# schematic-version4_-_Jingbin.net
KiCad netlist of a schematic drawn in EAGLE
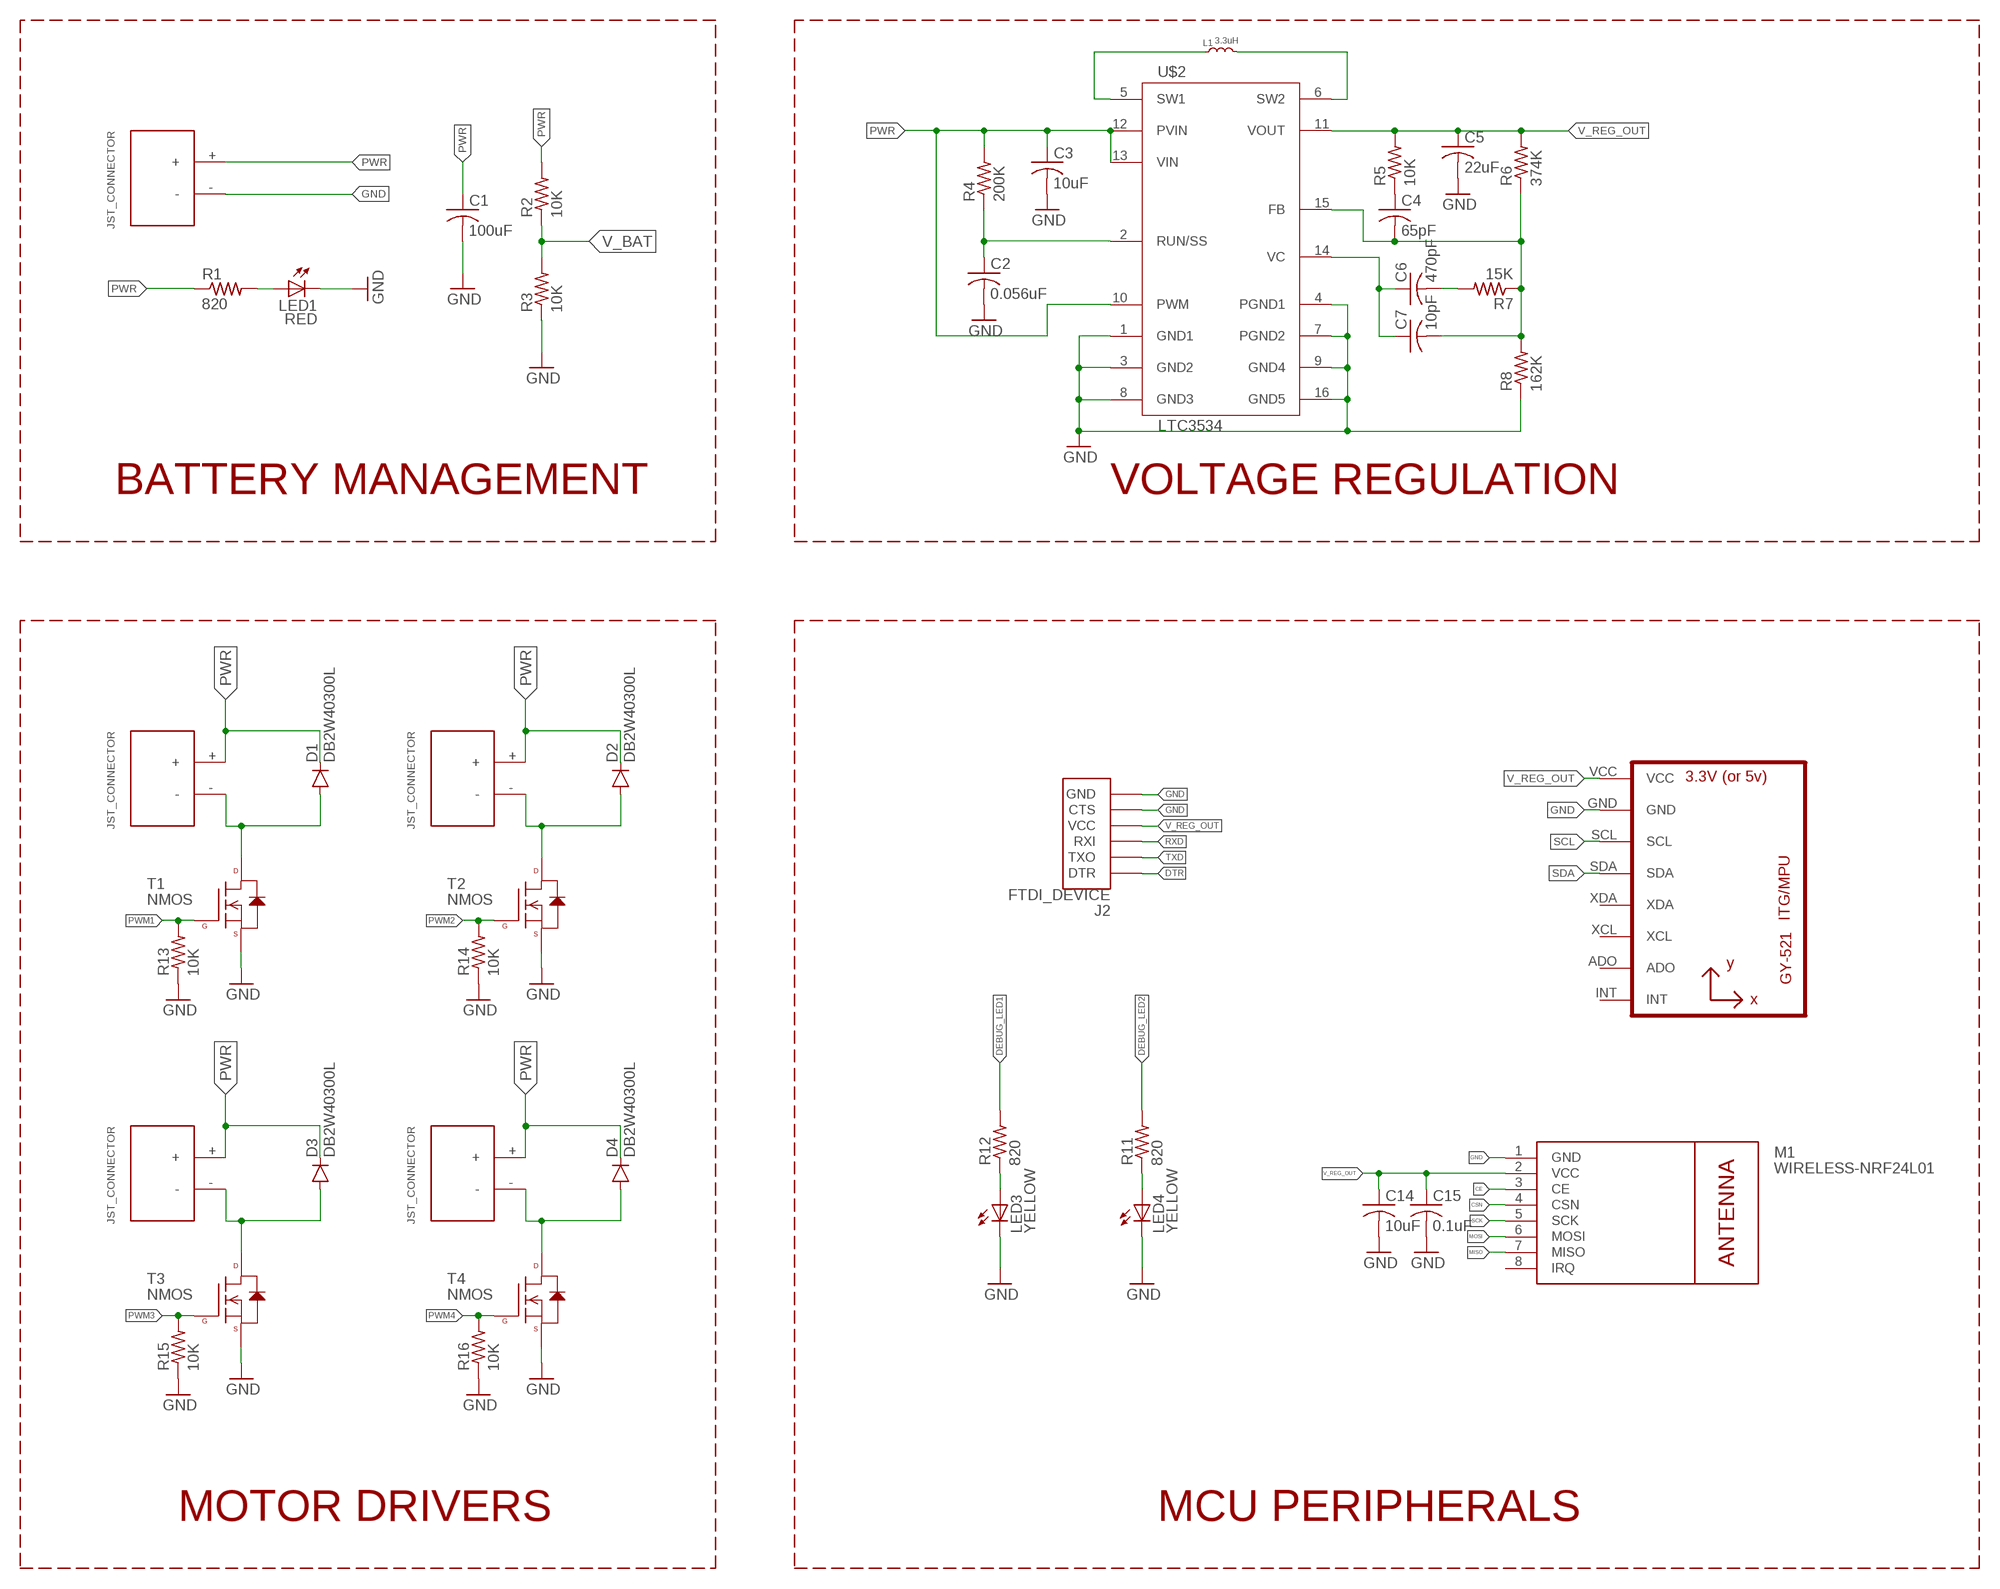
[diagram p0: schematic, sheet 1, part 1 of 2]
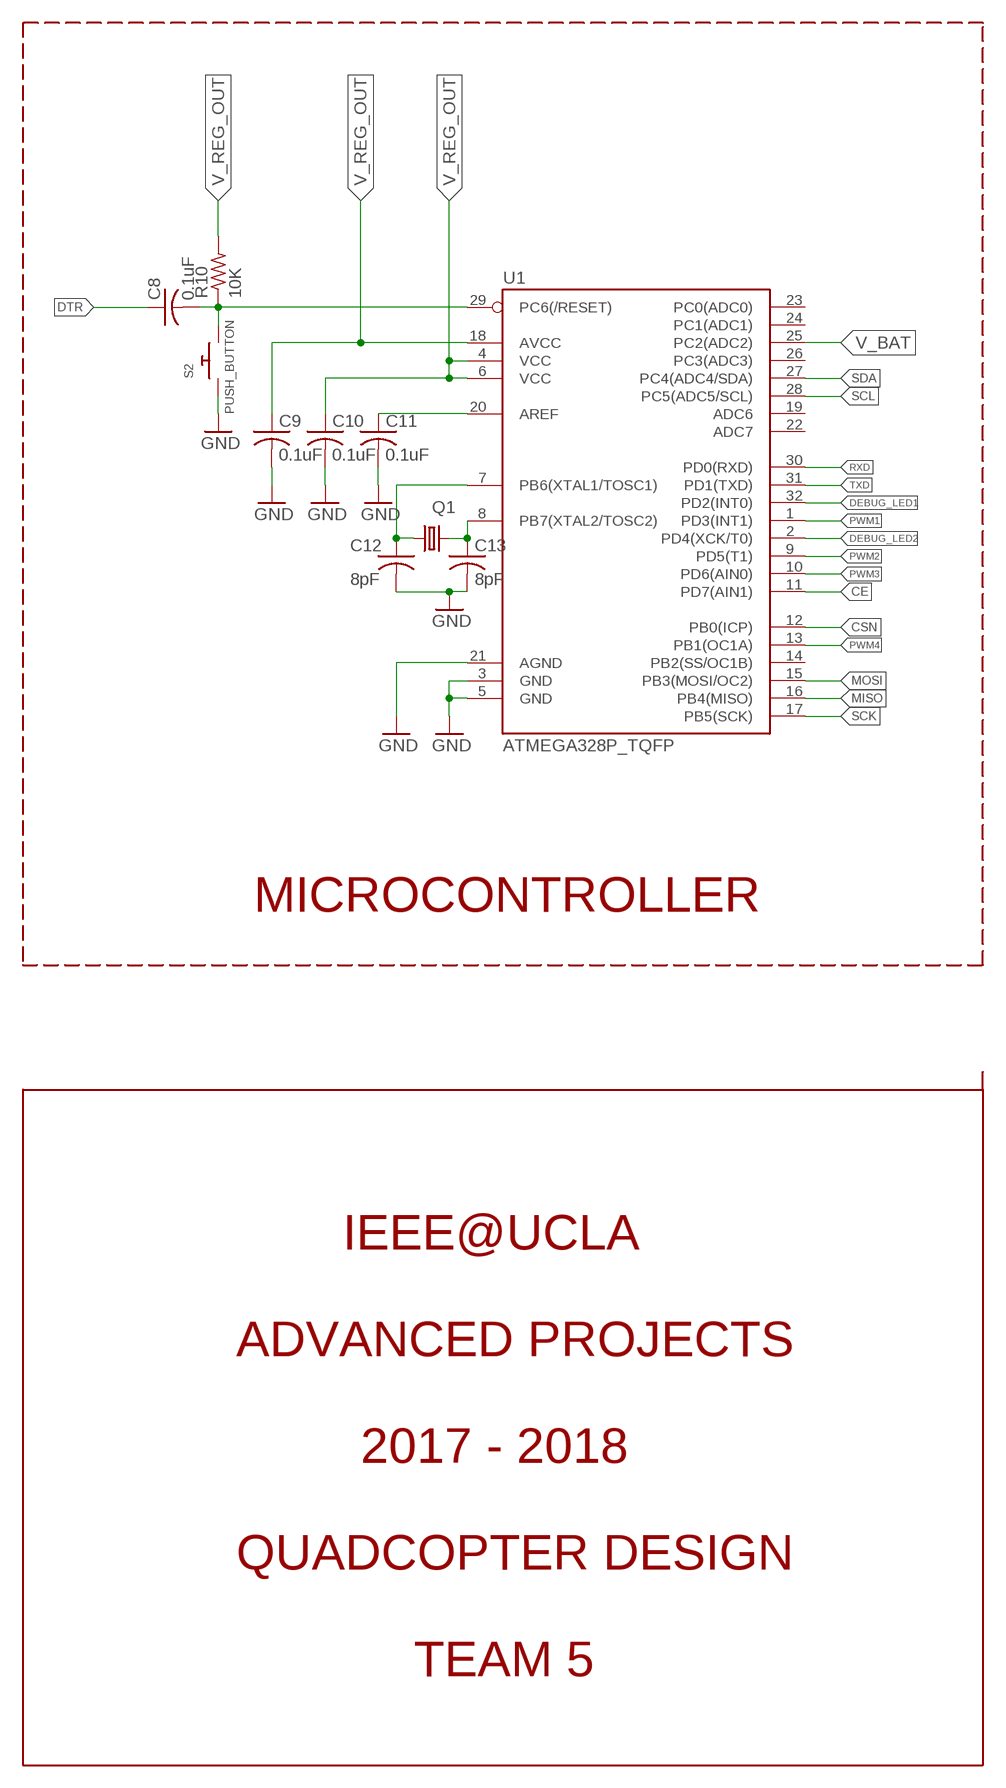
[diagram p1: schematic, sheet 1, part 2 of 2]

(export (version "E")
  (design (tool "Eeschema 10.0.6"))
  (components
    (comp (ref "C1")
      (value "100uF")
      (footprint "eagle-import:C1206")
      (libsource (lib "eagle-import") (part "C-USC1206"))
    )
    (comp (ref "C2")
      (value "0.056uF")
      (footprint "eagle-import:C0603")
      (libsource (lib "eagle-import") (part "resistor_348_C-USC0603"))
    )
    (comp (ref "C3")
      (value "10uF")
      (footprint "eagle-import:C0603")
      (libsource (lib "eagle-import") (part "resistor_348_C-USC0603"))
    )
    (comp (ref "C4")
      (value "65pF")
      (footprint "eagle-import:C1206")
      (libsource (lib "eagle-import") (part "C-USC1206"))
    )
    (comp (ref "C5")
      (value "22uF")
      (footprint "eagle-import:C0603")
      (libsource (lib "eagle-import") (part "resistor_348_C-USC0603"))
    )
    (comp (ref "C6")
      (value "470pF")
      (footprint "eagle-import:C0603")
      (libsource (lib "eagle-import") (part "resistor_348_C-USC0603"))
    )
    (comp (ref "C7")
      (value "10pF")
      (footprint "eagle-import:C0603")
      (libsource (lib "eagle-import") (part "resistor_348_C-USC0603"))
    )
    (comp (ref "C8")
      (value "0.1uF")
      (footprint "eagle-import:C0603")
      (libsource (lib "eagle-import") (part "C-USC0603"))
    )
    (comp (ref "C9")
      (value "0.1uF")
      (footprint "eagle-import:C0603")
      (libsource (lib "eagle-import") (part "C-USC0603"))
    )
    (comp (ref "C10")
      (value "0.1uF")
      (footprint "eagle-import:C0603")
      (libsource (lib "eagle-import") (part "C-USC0603"))
    )
    (comp (ref "C11")
      (value "0.1uF")
      (footprint "eagle-import:C0603")
      (libsource (lib "eagle-import") (part "C-USC0603"))
    )
    (comp (ref "C12")
      (value "8pF")
      (footprint "eagle-import:C0603")
      (libsource (lib "eagle-import") (part "resistor_348_C-USC0603"))
    )
    (comp (ref "C13")
      (value "8pF")
      (footprint "eagle-import:C0603")
      (libsource (lib "eagle-import") (part "resistor_348_C-USC0603"))
    )
    (comp (ref "C14")
      (value "10uF")
      (footprint "eagle-import:C0603")
      (libsource (lib "eagle-import") (part "resistor_348_C-USC0603"))
    )
    (comp (ref "C15")
      (value "0.1uF")
      (footprint "eagle-import:C0603")
      (libsource (lib "eagle-import") (part "resistor_348_C-USC0603"))
    )
    (comp (ref "D1")
      (value "DB2W40300L")
      (footprint "eagle-import:MINI2-F3-B")
      (libsource (lib "eagle-import") (part "DB2W40300L"))
    )
    (comp (ref "D2")
      (value "DB2W40300L")
      (footprint "eagle-import:MINI2-F3-B")
      (libsource (lib "eagle-import") (part "DB2W40300L"))
    )
    (comp (ref "D3")
      (value "DB2W40300L")
      (footprint "eagle-import:MINI2-F3-B")
      (libsource (lib "eagle-import") (part "DB2W40300L"))
    )
    (comp (ref "D4")
      (value "DB2W40300L")
      (footprint "eagle-import:MINI2-F3-B")
      (libsource (lib "eagle-import") (part "DB2W40300L"))
    )
    (comp (ref "J2")
      (value "FTDI_DEVICE")
      (footprint "eagle-import:FTDI_DEVICE_SIDE")
      (libsource (lib "eagle-import") (part "FTDI_DEVICE"))
    )
    (comp (ref "L1")
      (value "3.3uH")
      (footprint "eagle-import:XAL4020")
      (libsource (lib "eagle-import") (part "INDUCTOR.XAL4020"))
    )
    (comp (ref "LED1")
      (value "RED")
      (footprint "eagle-import:SML0603")
      (libsource (lib "eagle-import") (part "LEDSML0603"))
    )
    (comp (ref "LED3")
      (value "YELLOW")
      (footprint "eagle-import:SML0603")
      (libsource (lib "eagle-import") (part "LEDSML0603"))
    )
    (comp (ref "LED4")
      (value "YELLOW")
      (footprint "eagle-import:SML0603")
      (libsource (lib "eagle-import") (part "LEDSML0603"))
    )
    (comp (ref "M1")
      (value "WIRELESS-NRF24L01")
      (footprint "eagle-import:WIRELESS-NRF24L01")
      (libsource (lib "eagle-import") (part "WIRELESS-NRF24L01"))
    )
    (comp (ref "Q1")
      (value "NX3225GD")
      (footprint "eagle-import:NX3225GD-CRA-3")
      (libsource (lib "eagle-import") (part "NX3225GD"))
    )
    (comp (ref "R1")
      (value "820")
      (footprint "eagle-import:R0603")
      (libsource (lib "eagle-import") (part "R-US_R0603"))
    )
    (comp (ref "R2")
      (value "10K")
      (footprint "eagle-import:R0603")
      (libsource (lib "eagle-import") (part "resistor_348_R-US_R0603"))
    )
    (comp (ref "R3")
      (value "10K")
      (footprint "eagle-import:R0603")
      (libsource (lib "eagle-import") (part "resistor_348_R-US_R0603"))
    )
    (comp (ref "R4")
      (value "200K")
      (footprint "eagle-import:R0603")
      (libsource (lib "eagle-import") (part "resistor_348_R-US_R0603"))
    )
    (comp (ref "R5")
      (value "10K")
      (footprint "eagle-import:R0603")
      (libsource (lib "eagle-import") (part "resistor_348_R-US_R0603"))
    )
    (comp (ref "R6")
      (value "374K")
      (footprint "eagle-import:R0603")
      (libsource (lib "eagle-import") (part "resistor_348_R-US_R0603"))
    )
    (comp (ref "R7")
      (value "15K")
      (footprint "eagle-import:R0603")
      (libsource (lib "eagle-import") (part "resistor_348_R-US_R0603"))
    )
    (comp (ref "R8")
      (value "162K")
      (footprint "eagle-import:R0603")
      (libsource (lib "eagle-import") (part "resistor_348_R-US_R0603"))
    )
    (comp (ref "R10")
      (value "10K")
      (footprint "eagle-import:R0603")
      (libsource (lib "eagle-import") (part "resistor_348_R-US_R0603"))
    )
    (comp (ref "R11")
      (value "820")
      (footprint "eagle-import:R0603")
      (libsource (lib "eagle-import") (part "R-US_R0603"))
    )
    (comp (ref "R12")
      (value "820")
      (footprint "eagle-import:R0603")
      (libsource (lib "eagle-import") (part "R-US_R0603"))
    )
    (comp (ref "R13")
      (value "10K")
      (footprint "eagle-import:R0603")
      (libsource (lib "eagle-import") (part "resistor_348_R-US_R0603"))
    )
    (comp (ref "R14")
      (value "10K")
      (footprint "eagle-import:R0603")
      (libsource (lib "eagle-import") (part "resistor_348_R-US_R0603"))
    )
    (comp (ref "R15")
      (value "10K")
      (footprint "eagle-import:R0603")
      (libsource (lib "eagle-import") (part "resistor_348_R-US_R0603"))
    )
    (comp (ref "R16")
      (value "10K")
      (footprint "eagle-import:R0603")
      (libsource (lib "eagle-import") (part "resistor_348_R-US_R0603"))
    )
    (comp (ref "S2")
      (value "PUSH_BUTTON")
      (footprint "eagle-import:PUSHBUTTON_SMD_SJ")
      (libsource (lib "eagle-import") (part "SWITCH_PUSHBUTTONSOFTTOUCHSMD_SJ"))
    )
    (comp (ref "T1")
      (value "NMOS")
      (footprint "eagle-import:SOT23-3")
      (libsource (lib "eagle-import") (part "N-CHANNEL-MOSFET-IRLML6244TRPBF"))
    )
    (comp (ref "T2")
      (value "NMOS")
      (footprint "eagle-import:SOT23-3")
      (libsource (lib "eagle-import") (part "N-CHANNEL-MOSFET-IRLML6244TRPBF"))
    )
    (comp (ref "T3")
      (value "NMOS")
      (footprint "eagle-import:SOT23-3")
      (libsource (lib "eagle-import") (part "N-CHANNEL-MOSFET-IRLML6244TRPBF"))
    )
    (comp (ref "T4")
      (value "NMOS")
      (footprint "eagle-import:SOT23-3")
      (libsource (lib "eagle-import") (part "N-CHANNEL-MOSFET-IRLML6244TRPBF"))
    )
    (comp (ref "U$1")
      (value "JST_CONNECTOR_FEMALE")
      (footprint "eagle-import:JST_CONNECTOR_FEMALE")
      (libsource (lib "eagle-import") (part "JST_CONNECTOR_FEMALE"))
    )
    (comp (ref "U$2")
      (value "LTC3534")
      (footprint "eagle-import:SSOP-16GN")
      (libsource (lib "eagle-import") (part "LTC3534"))
    )
    (comp (ref "U$4")
      (value "JST_CONNECTOR_FEMALE")
      (footprint "eagle-import:JST_CONNECTOR_FEMALE")
      (libsource (lib "eagle-import") (part "JST_CONNECTOR_FEMALE"))
    )
    (comp (ref "U$7")
      (value "JST_CONNECTOR_FEMALE")
      (footprint "eagle-import:JST_CONNECTOR_FEMALE")
      (libsource (lib "eagle-import") (part "JST_CONNECTOR_FEMALE"))
    )
    (comp (ref "U$10")
      (value "JST_CONNECTOR_FEMALE")
      (footprint "eagle-import:JST_CONNECTOR_FEMALE")
      (libsource (lib "eagle-import") (part "JST_CONNECTOR_FEMALE"))
    )
    (comp (ref "U$13")
      (value "JST_CONNECTOR_FEMALE")
      (footprint "eagle-import:JST_CONNECTOR_FEMALE")
      (libsource (lib "eagle-import") (part "JST_CONNECTOR_FEMALE"))
    )
    (comp (ref "U1")
      (value "ATMEGA328P_TQFP")
      (footprint "eagle-import:TQFP32-08")
      (libsource (lib "eagle-import") (part "ATMEGA328P_TQFP"))
    )
    (comp (ref "U2")
      (value "GY-521MPU6050")
      (footprint "eagle-import:GY-521")
      (libsource (lib "eagle-import") (part "GY-521MPU6050"))
    )
  )
  (nets
    (net (code "1") (name "CE") (class "Default")
      (node (ref "M1") (pin "3") (pinfunction "CE_3") (pintype "bidirectional"))
      (node (ref "U1") (pin "11") (pinfunction "PD7(AIN1)_11") (pintype "bidirectional"))
    )
    (net (code "2") (name "CSN") (class "Default")
      (node (ref "M1") (pin "4") (pinfunction "CSN_4") (pintype "bidirectional"))
      (node (ref "U1") (pin "12") (pinfunction "PB0(ICP)_12") (pintype "bidirectional"))
    )
    (net (code "3") (name "DEBUG_LED1") (class "Default")
      (node (ref "R12") (pin "2") (pinfunction "2_2") (pintype "passive"))
      (node (ref "U1") (pin "32") (pinfunction "PD2(INT0)_32") (pintype "bidirectional"))
    )
    (net (code "4") (name "DEBUG_LED2") (class "Default")
      (node (ref "R11") (pin "2") (pinfunction "2_2") (pintype "passive"))
      (node (ref "U1") (pin "2") (pinfunction "PD4(XCK/T0)_2") (pintype "bidirectional"))
    )
    (net (code "5") (name "DTR") (class "Default")
      (node (ref "C8") (pin "1") (pinfunction "1_1") (pintype "passive"))
      (node (ref "J2") (pin "P$1") (pinfunction "DTR_P$1") (pintype "bidirectional"))
    )
    (net (code "6") (name "GND") (class "Default")
      (node (ref "C1") (pin "2") (pinfunction "2_2") (pintype "passive"))
      (node (ref "C10") (pin "2") (pinfunction "2_2") (pintype "passive"))
      (node (ref "C11") (pin "2") (pinfunction "2_2") (pintype "passive"))
      (node (ref "C12") (pin "2") (pinfunction "2_2") (pintype "passive"))
      (node (ref "C13") (pin "2") (pinfunction "2_2") (pintype "passive"))
      (node (ref "C14") (pin "2") (pinfunction "2_2") (pintype "passive"))
      (node (ref "C15") (pin "2") (pinfunction "2_2") (pintype "passive"))
      (node (ref "C2") (pin "2") (pinfunction "2_2") (pintype "passive"))
      (node (ref "C3") (pin "2") (pinfunction "2_2") (pintype "passive"))
      (node (ref "C5") (pin "2") (pinfunction "2_2") (pintype "passive"))
      (node (ref "C9") (pin "2") (pinfunction "2_2") (pintype "passive"))
      (node (ref "J2") (pin "P$5") (pinfunction "CTS_P$5") (pintype "bidirectional"))
      (node (ref "J2") (pin "P$6") (pinfunction "GND_P$6") (pintype "bidirectional"))
      (node (ref "LED1") (pin "C") (pinfunction "C_C") (pintype "passive"))
      (node (ref "LED3") (pin "C") (pinfunction "C_C") (pintype "passive"))
      (node (ref "LED4") (pin "C") (pinfunction "C_C") (pintype "passive"))
      (node (ref "M1") (pin "1") (pinfunction "GND_1") (pintype "power_in"))
      (node (ref "R13") (pin "1") (pinfunction "1_1") (pintype "passive"))
      (node (ref "R14") (pin "1") (pinfunction "1_1") (pintype "passive"))
      (node (ref "R15") (pin "1") (pinfunction "1_1") (pintype "passive"))
      (node (ref "R16") (pin "1") (pinfunction "1_1") (pintype "passive"))
      (node (ref "R3") (pin "1") (pinfunction "1_1") (pintype "passive"))
      (node (ref "R8") (pin "1") (pinfunction "1_1") (pintype "passive"))
      (node (ref "S2") (pin "P$1") (pinfunction "P$1_P$1") (pintype "passive"))
      (node (ref "T1") (pin "2") (pinfunction "S_2") (pintype "passive"))
      (node (ref "T2") (pin "2") (pinfunction "S_2") (pintype "passive"))
      (node (ref "T3") (pin "2") (pinfunction "S_2") (pintype "passive"))
      (node (ref "T4") (pin "2") (pinfunction "S_2") (pintype "passive"))
      (node (ref "U$1") (pin "-") (pinfunction "-_-") (pintype "bidirectional"))
      (node (ref "U$2") (pin "1") (pinfunction "GND1_1") (pintype "bidirectional"))
      (node (ref "U$2") (pin "16") (pinfunction "GND5_16") (pintype "bidirectional"))
      (node (ref "U$2") (pin "3") (pinfunction "GND2_3") (pintype "bidirectional"))
      (node (ref "U$2") (pin "4") (pinfunction "PGND1_4") (pintype "bidirectional"))
      (node (ref "U$2") (pin "7") (pinfunction "PGND2_7") (pintype "bidirectional"))
      (node (ref "U$2") (pin "8") (pinfunction "GND3_8") (pintype "bidirectional"))
      (node (ref "U$2") (pin "9") (pinfunction "GND4_9") (pintype "bidirectional"))
      (node (ref "U1") (pin "21") (pinfunction "AGND_21") (pintype "bidirectional"))
      (node (ref "U1") (pin "3") (pinfunction "GND_3") (pintype "bidirectional"))
      (node (ref "U1") (pin "5") (pinfunction "GND_5") (pintype "bidirectional"))
      (node (ref "U2") (pin "GND") (pinfunction "GND_GND") (pintype "bidirectional"))
    )
    (net (code "7") (name "MISO") (class "Default")
      (node (ref "M1") (pin "7") (pinfunction "MISO_7") (pintype "bidirectional"))
      (node (ref "U1") (pin "16") (pinfunction "PB4(MISO)_16") (pintype "bidirectional"))
    )
    (net (code "8") (name "MOSI") (class "Default")
      (node (ref "M1") (pin "6") (pinfunction "MOSI_6") (pintype "bidirectional"))
      (node (ref "U1") (pin "15") (pinfunction "PB3(MOSI/OC2)_15") (pintype "bidirectional"))
    )
    (net (code "9") (name "Net-(C4-Pad1)") (class "Default")
      (node (ref "C4") (pin "1") (pinfunction "1_1") (pintype "passive"))
      (node (ref "R5") (pin "1") (pinfunction "1_1") (pintype "passive"))
    )
    (net (code "10") (name "Net-(C6-Pad2)") (class "Default")
      (node (ref "C6") (pin "2") (pinfunction "2_2") (pintype "passive"))
      (node (ref "R7") (pin "2") (pinfunction "2_2") (pintype "passive"))
    )
    (net (code "11") (name "Net-(D1-PPIN)") (class "Default")
      (node (ref "D1") (pin "POS") (pinfunction "PPIN_POS") (pintype "passive"))
      (node (ref "T1") (pin "3") (pinfunction "D_3") (pintype "passive"))
      (node (ref "U$4") (pin "-") (pinfunction "-_-") (pintype "bidirectional"))
    )
    (net (code "12") (name "Net-(D2-PPIN)") (class "Default")
      (node (ref "D2") (pin "POS") (pinfunction "PPIN_POS") (pintype "passive"))
      (node (ref "T2") (pin "3") (pinfunction "D_3") (pintype "passive"))
      (node (ref "U$7") (pin "-") (pinfunction "-_-") (pintype "bidirectional"))
    )
    (net (code "13") (name "Net-(D3-PPIN)") (class "Default")
      (node (ref "D3") (pin "POS") (pinfunction "PPIN_POS") (pintype "passive"))
      (node (ref "T3") (pin "3") (pinfunction "D_3") (pintype "passive"))
      (node (ref "U$10") (pin "-") (pinfunction "-_-") (pintype "bidirectional"))
    )
    (net (code "14") (name "Net-(D4-PPIN)") (class "Default")
      (node (ref "D4") (pin "POS") (pinfunction "PPIN_POS") (pintype "passive"))
      (node (ref "T4") (pin "3") (pinfunction "D_3") (pintype "passive"))
      (node (ref "U$13") (pin "-") (pinfunction "-_-") (pintype "bidirectional"))
    )
    (net (code "15") (name "Net-(LED1-PadA)") (class "Default")
      (node (ref "LED1") (pin "A") (pinfunction "A_A") (pintype "passive"))
      (node (ref "R1") (pin "2") (pinfunction "2_2") (pintype "passive"))
    )
    (net (code "16") (name "Net-(LED3-PadA)") (class "Default")
      (node (ref "LED3") (pin "A") (pinfunction "A_A") (pintype "passive"))
      (node (ref "R12") (pin "1") (pinfunction "1_1") (pintype "passive"))
    )
    (net (code "17") (name "Net-(LED4-PadA)") (class "Default")
      (node (ref "LED4") (pin "A") (pinfunction "A_A") (pintype "passive"))
      (node (ref "R11") (pin "1") (pinfunction "1_1") (pintype "passive"))
    )
    (net (code "18") (name "Net-(Q1-1)") (class "Default")
      (node (ref "C12") (pin "1") (pinfunction "1_1") (pintype "passive"))
      (node (ref "Q1") (pin "P$1") (pinfunction "1_P$1") (pintype "passive"))
      (node (ref "U1") (pin "7") (pinfunction "PB6(XTAL1/TOSC1)_7") (pintype "bidirectional"))
    )
    (net (code "19") (name "Net-(Q1-2)") (class "Default")
      (node (ref "C13") (pin "1") (pinfunction "1_1") (pintype "passive"))
      (node (ref "Q1") (pin "P$2") (pinfunction "2_P$2") (pintype "passive"))
      (node (ref "U1") (pin "8") (pinfunction "PB7(XTAL2/TOSC2)_8") (pintype "bidirectional"))
    )
    (net (code "20") (name "Net-(U$2-FB)") (class "Default")
      (node (ref "C4") (pin "2") (pinfunction "2_2") (pintype "passive"))
      (node (ref "C7") (pin "2") (pinfunction "2_2") (pintype "passive"))
      (node (ref "R6") (pin "1") (pinfunction "1_1") (pintype "passive"))
      (node (ref "R7") (pin "1") (pinfunction "1_1") (pintype "passive"))
      (node (ref "R8") (pin "2") (pinfunction "2_2") (pintype "passive"))
      (node (ref "U$2") (pin "15") (pinfunction "FB_15") (pintype "bidirectional"))
    )
    (net (code "21") (name "Net-(U$2-RUN{slash}SS)") (class "Default")
      (node (ref "C2") (pin "1") (pinfunction "1_1") (pintype "passive"))
      (node (ref "R4") (pin "1") (pinfunction "1_1") (pintype "passive"))
      (node (ref "U$2") (pin "2") (pinfunction "RUN/SS_2") (pintype "bidirectional"))
    )
    (net (code "22") (name "Net-(U$2-SW1)") (class "Default")
      (node (ref "L1") (pin "1") (pinfunction "1_1") (pintype "passive"))
      (node (ref "U$2") (pin "5") (pinfunction "SW1_5") (pintype "bidirectional"))
    )
    (net (code "23") (name "Net-(U$2-SW2)") (class "Default")
      (node (ref "L1") (pin "2") (pinfunction "2_2") (pintype "passive"))
      (node (ref "U$2") (pin "6") (pinfunction "SW2_6") (pintype "bidirectional"))
    )
    (net (code "24") (name "Net-(U$2-VC)") (class "Default")
      (node (ref "C6") (pin "1") (pinfunction "1_1") (pintype "passive"))
      (node (ref "C7") (pin "1") (pinfunction "1_1") (pintype "passive"))
      (node (ref "U$2") (pin "14") (pinfunction "VC_14") (pintype "bidirectional"))
    )
    (net (code "25") (name "Net-(U1-AREF)") (class "Default")
      (node (ref "C11") (pin "1") (pinfunction "1_1") (pintype "passive"))
      (node (ref "U1") (pin "20") (pinfunction "AREF_20") (pintype "bidirectional"))
    )
    (net (code "26") (name "Net-(U1-PC6({slash}RESET))") (class "Default")
      (node (ref "C8") (pin "2") (pinfunction "2_2") (pintype "passive"))
      (node (ref "R10") (pin "1") (pinfunction "1_1") (pintype "passive"))
      (node (ref "S2") (pin "P$2") (pinfunction "P$2_P$2") (pintype "passive"))
      (node (ref "U1") (pin "29") (pinfunction "PC6(/RESET)_29") (pintype "bidirectional"))
    )
    (net (code "27") (name "PWM1") (class "Default")
      (node (ref "R13") (pin "2") (pinfunction "2_2") (pintype "passive"))
      (node (ref "T1") (pin "1") (pinfunction "G_1") (pintype "passive"))
      (node (ref "U1") (pin "1") (pinfunction "PD3(INT1)_1") (pintype "bidirectional"))
    )
    (net (code "28") (name "PWM2") (class "Default")
      (node (ref "R14") (pin "2") (pinfunction "2_2") (pintype "passive"))
      (node (ref "T2") (pin "1") (pinfunction "G_1") (pintype "passive"))
      (node (ref "U1") (pin "9") (pinfunction "PD5(T1)_9") (pintype "bidirectional"))
    )
    (net (code "29") (name "PWM3") (class "Default")
      (node (ref "R15") (pin "2") (pinfunction "2_2") (pintype "passive"))
      (node (ref "T3") (pin "1") (pinfunction "G_1") (pintype "passive"))
      (node (ref "U1") (pin "10") (pinfunction "PD6(AIN0)_10") (pintype "bidirectional"))
    )
    (net (code "30") (name "PWM4") (class "Default")
      (node (ref "R16") (pin "2") (pinfunction "2_2") (pintype "passive"))
      (node (ref "T4") (pin "1") (pinfunction "G_1") (pintype "passive"))
      (node (ref "U1") (pin "13") (pinfunction "PB1(OC1A)_13") (pintype "bidirectional"))
    )
    (net (code "31") (name "PWR") (class "Default")
      (node (ref "C1") (pin "1") (pinfunction "1_1") (pintype "passive"))
      (node (ref "C3") (pin "1") (pinfunction "1_1") (pintype "passive"))
      (node (ref "D1") (pin "NEG") (pinfunction "GPIN_NEG") (pintype "passive"))
      (node (ref "D2") (pin "NEG") (pinfunction "GPIN_NEG") (pintype "passive"))
      (node (ref "D3") (pin "NEG") (pinfunction "GPIN_NEG") (pintype "passive"))
      (node (ref "D4") (pin "NEG") (pinfunction "GPIN_NEG") (pintype "passive"))
      (node (ref "R1") (pin "1") (pinfunction "1_1") (pintype "passive"))
      (node (ref "R2") (pin "2") (pinfunction "2_2") (pintype "passive"))
      (node (ref "R4") (pin "2") (pinfunction "2_2") (pintype "passive"))
      (node (ref "U$1") (pin "+") (pinfunction "+_+") (pintype "bidirectional"))
      (node (ref "U$10") (pin "+") (pinfunction "+_+") (pintype "bidirectional"))
      (node (ref "U$13") (pin "+") (pinfunction "+_+") (pintype "bidirectional"))
      (node (ref "U$2") (pin "10") (pinfunction "PWM_10") (pintype "bidirectional"))
      (node (ref "U$2") (pin "12") (pinfunction "PVIN_12") (pintype "bidirectional"))
      (node (ref "U$2") (pin "13") (pinfunction "VIN_13") (pintype "bidirectional"))
      (node (ref "U$4") (pin "+") (pinfunction "+_+") (pintype "bidirectional"))
      (node (ref "U$7") (pin "+") (pinfunction "+_+") (pintype "bidirectional"))
    )
    (net (code "32") (name "RXD") (class "Default")
      (node (ref "J2") (pin "P$3") (pinfunction "RXI_P$3") (pintype "bidirectional"))
      (node (ref "U1") (pin "30") (pinfunction "PD0(RXD)_30") (pintype "bidirectional"))
    )
    (net (code "33") (name "SCK") (class "Default")
      (node (ref "M1") (pin "5") (pinfunction "SCK_5") (pintype "bidirectional"))
      (node (ref "U1") (pin "17") (pinfunction "PB5(SCK)_17") (pintype "bidirectional"))
    )
    (net (code "34") (name "SCL") (class "Default")
      (node (ref "U1") (pin "28") (pinfunction "PC5(ADC5/SCL)_28") (pintype "bidirectional"))
      (node (ref "U2") (pin "SCL") (pinfunction "SCL_SCL") (pintype "bidirectional"))
    )
    (net (code "35") (name "SDA") (class "Default")
      (node (ref "U1") (pin "27") (pinfunction "PC4(ADC4/SDA)_27") (pintype "bidirectional"))
      (node (ref "U2") (pin "SDA") (pinfunction "SDA_SDA") (pintype "bidirectional"))
    )
    (net (code "36") (name "TXD") (class "Default")
      (node (ref "J2") (pin "P$2") (pinfunction "TXO_P$2") (pintype "bidirectional"))
      (node (ref "U1") (pin "31") (pinfunction "PD1(TXD)_31") (pintype "bidirectional"))
    )
    (net (code "37") (name "V_BAT") (class "Default")
      (node (ref "R2") (pin "1") (pinfunction "1_1") (pintype "passive"))
      (node (ref "R3") (pin "2") (pinfunction "2_2") (pintype "passive"))
      (node (ref "U1") (pin "25") (pinfunction "PC2(ADC2)_25") (pintype "bidirectional"))
    )
    (net (code "38") (name "V_REG_OUT") (class "Default")
      (node (ref "C10") (pin "1") (pinfunction "1_1") (pintype "passive"))
      (node (ref "C14") (pin "1") (pinfunction "1_1") (pintype "passive"))
      (node (ref "C15") (pin "1") (pinfunction "1_1") (pintype "passive"))
      (node (ref "C5") (pin "1") (pinfunction "1_1") (pintype "passive"))
      (node (ref "C9") (pin "1") (pinfunction "1_1") (pintype "passive"))
      (node (ref "J2") (pin "P$4") (pinfunction "VCC_P$4") (pintype "bidirectional"))
      (node (ref "M1") (pin "2") (pinfunction "VCC_2") (pintype "power_in"))
      (node (ref "R10") (pin "2") (pinfunction "2_2") (pintype "passive"))
      (node (ref "R5") (pin "2") (pinfunction "2_2") (pintype "passive"))
      (node (ref "R6") (pin "2") (pinfunction "2_2") (pintype "passive"))
      (node (ref "U$2") (pin "11") (pinfunction "VOUT_11") (pintype "bidirectional"))
      (node (ref "U1") (pin "18") (pinfunction "AVCC_18") (pintype "bidirectional"))
      (node (ref "U1") (pin "4") (pinfunction "VCC_4") (pintype "bidirectional"))
      (node (ref "U1") (pin "6") (pinfunction "VCC_6") (pintype "bidirectional"))
      (node (ref "U2") (pin "VCC") (pinfunction "VCC_VCC") (pintype "bidirectional"))
    )
    (net (code "39") (name "unconnected-(M1-IRQ-Pad8)") (class "Default")
      (node (ref "M1") (pin "8") (pinfunction "IRQ_8") (pintype "bidirectional"))
    )
    (net (code "40") (name "unconnected-(U1-ADC6-Pad19)") (class "Default")
      (node (ref "U1") (pin "19") (pinfunction "ADC6_19") (pintype "bidirectional"))
    )
    (net (code "41") (name "unconnected-(U1-ADC7-Pad22)") (class "Default")
      (node (ref "U1") (pin "22") (pinfunction "ADC7_22") (pintype "bidirectional"))
    )
    (net (code "42") (name "unconnected-(U1-PB2(SS{slash}OC1B)-Pad14)") (class "Default")
      (node (ref "U1") (pin "14") (pinfunction "PB2(SS/OC1B)_14") (pintype "bidirectional"))
    )
    (net (code "43") (name "unconnected-(U1-PC0(ADC0)-Pad23)") (class "Default")
      (node (ref "U1") (pin "23") (pinfunction "PC0(ADC0)_23") (pintype "bidirectional"))
    )
    (net (code "44") (name "unconnected-(U1-PC1(ADC1)-Pad24)") (class "Default")
      (node (ref "U1") (pin "24") (pinfunction "PC1(ADC1)_24") (pintype "bidirectional"))
    )
    (net (code "45") (name "unconnected-(U1-PC3(ADC3)-Pad26)") (class "Default")
      (node (ref "U1") (pin "26") (pinfunction "PC3(ADC3)_26") (pintype "bidirectional"))
    )
    (net (code "46") (name "unconnected-(U2-PadADO)") (class "Default")
      (node (ref "U2") (pin "ADO") (pinfunction "ADO_ADO") (pintype "bidirectional"))
    )
    (net (code "47") (name "unconnected-(U2-PadINT)") (class "Default")
      (node (ref "U2") (pin "INT") (pinfunction "INT_INT") (pintype "bidirectional"))
    )
    (net (code "48") (name "unconnected-(U2-PadXCL)") (class "Default")
      (node (ref "U2") (pin "XCL") (pinfunction "XCL_XCL") (pintype "bidirectional"))
    )
    (net (code "49") (name "unconnected-(U2-PadXDA)") (class "Default")
      (node (ref "U2") (pin "XDA") (pinfunction "XDA_XDA") (pintype "bidirectional"))
    )
  )
)
